# Fan-Controller.net
KiCad netlist of a schematic drawn in EAGLE
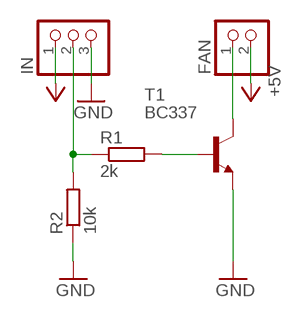
[diagram p0: schematic, sheet 1]

(export (version "E")
  (design (tool "Eeschema 10.0.6"))
  (components
    (comp (ref "FAN")
      (value "PINHD-1X2/90")
      (footprint "eagle-import:1X02_90")
      (libsource (lib "eagle-import") (part "PINHD-1X2/90"))
    )
    (comp (ref "IN")
      (value "PINHD-1X3/90")
      (footprint "eagle-import:1X03_90")
      (libsource (lib "eagle-import") (part "PINHD-1X3/90"))
    )
    (comp (ref "R1")
      (value "2k")
      (footprint "eagle-import:0204_7")
      (libsource (lib "eagle-import") (part "R-EU_0204/7"))
    )
    (comp (ref "R2")
      (value "10k")
      (footprint "eagle-import:0204_7")
      (libsource (lib "eagle-import") (part "R-EU_0204/7"))
    )
    (comp (ref "T1")
      (value "BC337")
      (footprint "eagle-import:TO92")
      (libsource (lib "eagle-import") (part "BC337"))
    )
  )
  (nets
    (net (code "1") (name "+5V") (class "Default")
      (node (ref "FAN") (pin "2") (pinfunction "2_2") (pintype "passive"))
      (node (ref "IN") (pin "1") (pinfunction "1_1") (pintype "passive"))
    )
    (net (code "2") (name "GND") (class "Default")
      (node (ref "IN") (pin "3") (pinfunction "3_3") (pintype "passive"))
      (node (ref "R2") (pin "1") (pinfunction "1_1") (pintype "passive"))
      (node (ref "T1") (pin "1") (pinfunction "E_1") (pintype "passive"))
    )
    (net (code "3") (name "Net-(IN-Pad2)") (class "Default")
      (node (ref "IN") (pin "2") (pinfunction "2_2") (pintype "passive"))
      (node (ref "R1") (pin "1") (pinfunction "1_1") (pintype "passive"))
      (node (ref "R2") (pin "2") (pinfunction "2_2") (pintype "passive"))
    )
    (net (code "4") (name "Net-(T1-B)") (class "Default")
      (node (ref "R1") (pin "2") (pinfunction "2_2") (pintype "passive"))
      (node (ref "T1") (pin "2") (pinfunction "B_2") (pintype "passive"))
    )
    (net (code "5") (name "Net-(T1-C)") (class "Default")
      (node (ref "FAN") (pin "1") (pinfunction "1_1") (pintype "passive"))
      (node (ref "T1") (pin "3") (pinfunction "C_3") (pintype "passive"))
    )
  )
)
